# HB-Dis-EP-42BW.net
KiCad netlist of a schematic drawn in EAGLE
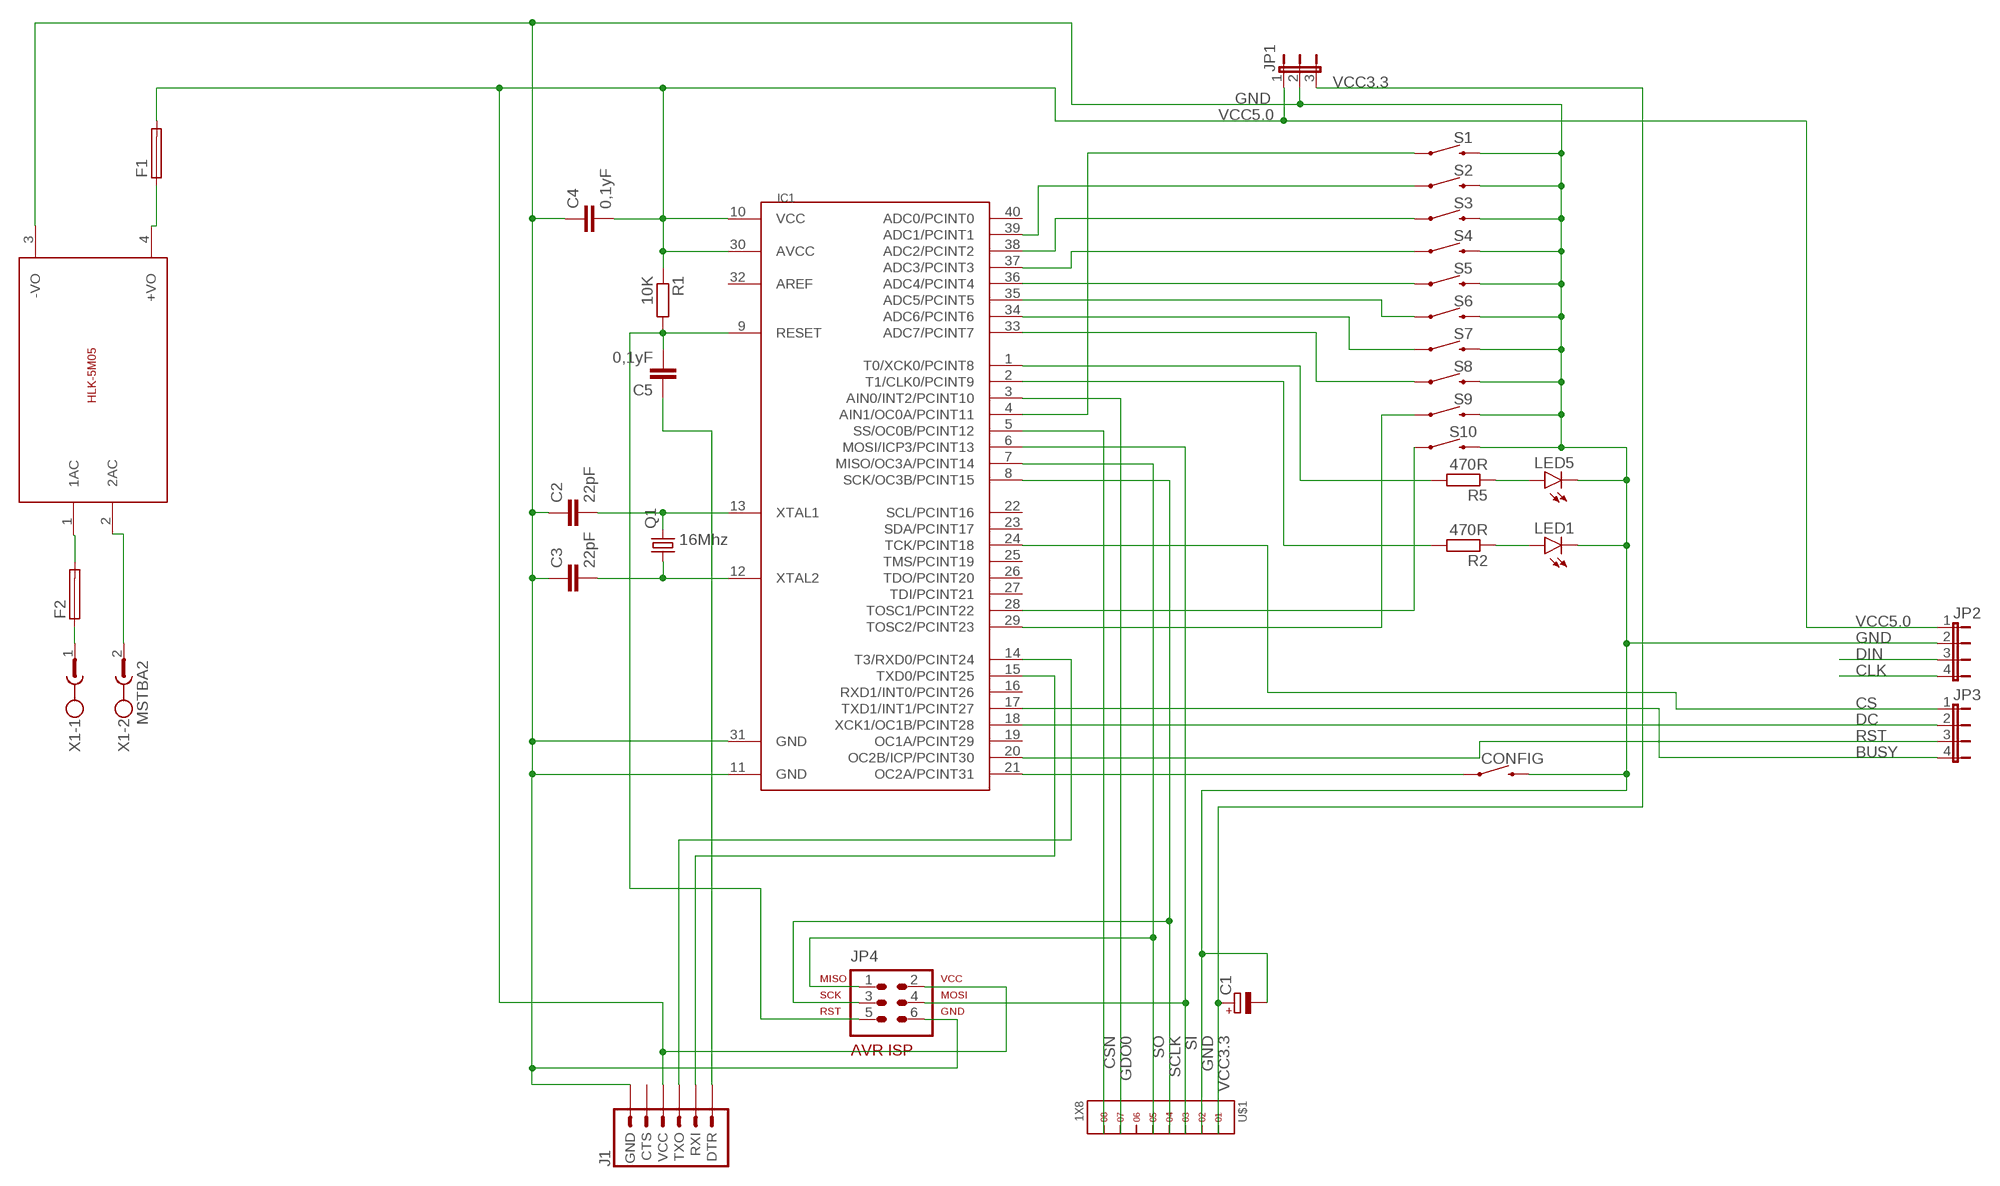
[diagram p0: schematic, sheet 1]

(export (version "E")
  (design (tool "Eeschema 10.0.6"))
  (components
    (comp (ref "C1")
      (value "CPOL-EUE2.5-5")
      (footprint "eagle-import:E2,5-5")
      (libsource (lib "eagle-import") (part "CPOL-EUE2.5-5"))
    )
    (comp (ref "C2")
      (value "22pF")
      (footprint "eagle-import:C025-024X044")
      (libsource (lib "eagle-import") (part "C-EU025-024X044"))
    )
    (comp (ref "C3")
      (value "22pF")
      (footprint "eagle-import:C025-024X044")
      (libsource (lib "eagle-import") (part "C-EU025-024X044"))
    )
    (comp (ref "C4")
      (value "0,1yF")
      (footprint "eagle-import:C025-024X044")
      (libsource (lib "eagle-import") (part "C-EU025-024X044"))
    )
    (comp (ref "C5")
      (value "0,1yF")
      (footprint "eagle-import:C025-024X044")
      (libsource (lib "eagle-import") (part "C-EU025-024X044"))
    )
    (comp (ref "CONFIG")
      (value "MOMENTARY-SWITCH-SPST-PTH-6.0MM-KIT")
      (footprint "eagle-import:TACTILE_SWITCH_PTH_6.0MM_KIT")
      (libsource (lib "eagle-import") (part "MOMENTARY-SWITCH-SPST-PTH-6.0MM-KIT"))
    )
    (comp (ref "F1")
      (value "SH22,5A")
      (footprint "eagle-import:SH22,5A")
      (fields (field (name "MPN") "0031.7701.11"))
      (libsource (lib "eagle-import") (part "SH22,5A"))
    )
    (comp (ref "F2")
      (value "SH22,5A")
      (footprint "eagle-import:SH22,5A")
      (fields (field (name "MPN") "0031.7701.11"))
      (libsource (lib "eagle-import") (part "SH22,5A"))
    )
    (comp (ref "IC1")
      (value "MEGA1284P")
      (footprint "eagle-import:DIL40")
      (libsource (lib "eagle-import") (part "MEGA1284P"))
    )
    (comp (ref "J1")
      (value "6_PIN_SERIAL_TARGETLONGPADS")
      (footprint "eagle-import:1X06_LONGPADS")
      (libsource (lib "eagle-import") (part "6_PIN_SERIAL_TARGETLONGPADS"))
    )
    (comp (ref "JP1")
      (value "JP2E")
      (footprint "eagle-import:JP2")
      (libsource (lib "eagle-import") (part "JP2E"))
    )
    (comp (ref "JP2")
      (value "JP4E")
      (footprint "eagle-import:JP4")
      (libsource (lib "eagle-import") (part "JP4E"))
    )
    (comp (ref "JP3")
      (value "JP4E")
      (footprint "eagle-import:JP4")
      (libsource (lib "eagle-import") (part "JP4E"))
    )
    (comp (ref "JP4")
      (value "AVR-ISP-6VERT")
      (footprint "eagle-import:AVR-ISP-6")
      (libsource (lib "eagle-import") (part "AVR-ISP-6VERT"))
    )
    (comp (ref "LED1")
      (value "LED3MM")
      (footprint "eagle-import:LED3MM")
      (libsource (lib "eagle-import") (part "LED3MM"))
    )
    (comp (ref "LED5")
      (value "LED3MM")
      (footprint "eagle-import:LED3MM")
      (libsource (lib "eagle-import") (part "LED3MM"))
    )
    (comp (ref "Q1")
      (value "16Mhz")
      (footprint "eagle-import:HC49U-V")
      (libsource (lib "eagle-import") (part "CRYSTALHC49U-V"))
    )
    (comp (ref "R1")
      (value "10K")
      (footprint "eagle-import:0309_10")
      (libsource (lib "eagle-import") (part "R-EU_0309/10"))
    )
    (comp (ref "R2")
      (value "470R")
      (footprint "eagle-import:0309_10")
      (libsource (lib "eagle-import") (part "R-EU_0309/10"))
    )
    (comp (ref "R5")
      (value "470R")
      (footprint "eagle-import:0309_10")
      (libsource (lib "eagle-import") (part "R-EU_0309/10"))
    )
    (comp (ref "S1")
      (value "MOMENTARY-SWITCH-SPST-PTH-6.0MM-KIT")
      (footprint "eagle-import:TACTILE_SWITCH_PTH_6.0MM_KIT")
      (libsource (lib "eagle-import") (part "MOMENTARY-SWITCH-SPST-PTH-6.0MM-KIT"))
    )
    (comp (ref "S2")
      (value "MOMENTARY-SWITCH-SPST-PTH-6.0MM-KIT")
      (footprint "eagle-import:TACTILE_SWITCH_PTH_6.0MM_KIT")
      (libsource (lib "eagle-import") (part "MOMENTARY-SWITCH-SPST-PTH-6.0MM-KIT"))
    )
    (comp (ref "S3")
      (value "MOMENTARY-SWITCH-SPST-PTH-6.0MM-KIT")
      (footprint "eagle-import:TACTILE_SWITCH_PTH_6.0MM_KIT")
      (libsource (lib "eagle-import") (part "MOMENTARY-SWITCH-SPST-PTH-6.0MM-KIT"))
    )
    (comp (ref "S4")
      (value "MOMENTARY-SWITCH-SPST-PTH-6.0MM-KIT")
      (footprint "eagle-import:TACTILE_SWITCH_PTH_6.0MM_KIT")
      (libsource (lib "eagle-import") (part "MOMENTARY-SWITCH-SPST-PTH-6.0MM-KIT"))
    )
    (comp (ref "S5")
      (value "MOMENTARY-SWITCH-SPST-PTH-6.0MM-KIT")
      (footprint "eagle-import:TACTILE_SWITCH_PTH_6.0MM_KIT")
      (libsource (lib "eagle-import") (part "MOMENTARY-SWITCH-SPST-PTH-6.0MM-KIT"))
    )
    (comp (ref "S6")
      (value "MOMENTARY-SWITCH-SPST-PTH-6.0MM-KIT")
      (footprint "eagle-import:TACTILE_SWITCH_PTH_6.0MM_KIT")
      (libsource (lib "eagle-import") (part "MOMENTARY-SWITCH-SPST-PTH-6.0MM-KIT"))
    )
    (comp (ref "S7")
      (value "MOMENTARY-SWITCH-SPST-PTH-6.0MM-KIT")
      (footprint "eagle-import:TACTILE_SWITCH_PTH_6.0MM_KIT")
      (libsource (lib "eagle-import") (part "MOMENTARY-SWITCH-SPST-PTH-6.0MM-KIT"))
    )
    (comp (ref "S8")
      (value "MOMENTARY-SWITCH-SPST-PTH-6.0MM-KIT")
      (footprint "eagle-import:TACTILE_SWITCH_PTH_6.0MM_KIT")
      (libsource (lib "eagle-import") (part "MOMENTARY-SWITCH-SPST-PTH-6.0MM-KIT"))
    )
    (comp (ref "S9")
      (value "MOMENTARY-SWITCH-SPST-PTH-6.0MM-KIT")
      (footprint "eagle-import:TACTILE_SWITCH_PTH_6.0MM_KIT")
      (libsource (lib "eagle-import") (part "MOMENTARY-SWITCH-SPST-PTH-6.0MM-KIT"))
    )
    (comp (ref "S10")
      (value "MOMENTARY-SWITCH-SPST-PTH-6.0MM-KIT")
      (footprint "eagle-import:TACTILE_SWITCH_PTH_6.0MM_KIT")
      (libsource (lib "eagle-import") (part "MOMENTARY-SWITCH-SPST-PTH-6.0MM-KIT"))
    )
    (comp (ref "U$1")
      (value "1X8")
      (footprint "eagle-import:1X8")
      (libsource (lib "eagle-import") (part "1X8"))
    )
    (comp (ref "U$3")
      (value "5VDC/5W")
      (footprint "eagle-import:HLK-5M05")
      (libsource (lib "eagle-import") (part "HLK-5M05"))
    )
    (comp (ref "X1")
      (value "MSTBA2")
      (footprint "eagle-import:MSTBA2")
      (fields (field (name "MF") "FARNELL") (field (name "MPN") "1757242"))
      (libsource (lib "eagle-import") (part "MSTBA2"))
    )
  )
  (nets
    (net (code "1") (name "/BUSY") (class "Default")
      (node (ref "IC1") (pin "17") (pinfunction "TXD1/INT1/PCINT27_17") (pintype "bidirectional"))
      (node (ref "JP3") (pin "4") (pinfunction "4_4") (pintype "passive"))
    )
    (net (code "2") (name "/CLK") (class "Default")
      (node (ref "JP2") (pin "4") (pinfunction "4_4") (pintype "passive"))
    )
    (net (code "3") (name "/CS") (class "Default")
      (node (ref "IC1") (pin "24") (pinfunction "TCK/PCINT18_24") (pintype "bidirectional"))
      (node (ref "JP3") (pin "1") (pinfunction "1_1") (pintype "passive"))
    )
    (net (code "4") (name "/CSN") (class "Default")
      (node (ref "IC1") (pin "5") (pinfunction "SS/OC0B/PCINT12_5") (pintype "bidirectional"))
      (node (ref "U$1") (pin "8") (pinfunction "8_8") (pintype "bidirectional"))
    )
    (net (code "5") (name "/DC") (class "Default")
      (node (ref "IC1") (pin "18") (pinfunction "XCK1/OC1B/PCINT28_18") (pintype "bidirectional"))
      (node (ref "JP3") (pin "2") (pinfunction "2_2") (pintype "passive"))
    )
    (net (code "6") (name "/DIN") (class "Default")
      (node (ref "JP2") (pin "3") (pinfunction "3_3") (pintype "passive"))
    )
    (net (code "7") (name "/GDO0") (class "Default")
      (node (ref "IC1") (pin "3") (pinfunction "AIN0/INT2/PCINT10_3") (pintype "bidirectional"))
      (node (ref "U$1") (pin "7") (pinfunction "7_7") (pintype "bidirectional"))
    )
    (net (code "8") (name "/GND") (class "Default")
      (node (ref "C1") (pin "-") (pinfunction "-_-") (pintype "passive"))
      (node (ref "C2") (pin "1") (pinfunction "1_1") (pintype "passive"))
      (node (ref "C3") (pin "1") (pinfunction "1_1") (pintype "passive"))
      (node (ref "C4") (pin "1") (pinfunction "1_1") (pintype "passive"))
      (node (ref "CONFIG") (pin "3") (pinfunction "2_3") (pintype "passive"))
      (node (ref "IC1") (pin "11") (pinfunction "GND_11") (pintype "bidirectional"))
      (node (ref "IC1") (pin "31") (pinfunction "GND_31") (pintype "bidirectional"))
      (node (ref "J1") (pin "6") (pinfunction "GND_6") (pintype "passive"))
      (node (ref "JP1") (pin "2") (pinfunction "2_2") (pintype "passive"))
      (node (ref "JP2") (pin "2") (pinfunction "2_2") (pintype "passive"))
      (node (ref "JP4") (pin "6") (pinfunction "6_6") (pintype "passive"))
      (node (ref "LED1") (pin "K") (pinfunction "C_K") (pintype "passive"))
      (node (ref "LED5") (pin "K") (pinfunction "C_K") (pintype "passive"))
      (node (ref "S1") (pin "3") (pinfunction "2_3") (pintype "passive"))
      (node (ref "S10") (pin "3") (pinfunction "2_3") (pintype "passive"))
      (node (ref "S2") (pin "3") (pinfunction "2_3") (pintype "passive"))
      (node (ref "S3") (pin "3") (pinfunction "2_3") (pintype "passive"))
      (node (ref "S4") (pin "3") (pinfunction "2_3") (pintype "passive"))
      (node (ref "S5") (pin "3") (pinfunction "2_3") (pintype "passive"))
      (node (ref "S6") (pin "3") (pinfunction "2_3") (pintype "passive"))
      (node (ref "S7") (pin "3") (pinfunction "2_3") (pintype "passive"))
      (node (ref "S8") (pin "3") (pinfunction "2_3") (pintype "passive"))
      (node (ref "S9") (pin "3") (pinfunction "2_3") (pintype "passive"))
      (node (ref "U$1") (pin "2") (pinfunction "2_2") (pintype "bidirectional"))
      (node (ref "U$3") (pin "3") (pinfunction "-VO_3") (pintype "bidirectional"))
    )
    (net (code "9") (name "/RST") (class "Default")
      (node (ref "IC1") (pin "20") (pinfunction "OC2B/ICP/PCINT30_20") (pintype "bidirectional"))
      (node (ref "JP3") (pin "3") (pinfunction "3_3") (pintype "passive"))
    )
    (net (code "10") (name "/SCLK") (class "Default")
      (node (ref "IC1") (pin "8") (pinfunction "SCK/OC3B/PCINT15_8") (pintype "bidirectional"))
      (node (ref "JP4") (pin "3") (pinfunction "3_3") (pintype "passive"))
      (node (ref "U$1") (pin "4") (pinfunction "4_4") (pintype "bidirectional"))
    )
    (net (code "11") (name "/SI") (class "Default")
      (node (ref "IC1") (pin "6") (pinfunction "MOSI/ICP3/PCINT13_6") (pintype "bidirectional"))
      (node (ref "JP4") (pin "4") (pinfunction "4_4") (pintype "passive"))
      (node (ref "U$1") (pin "3") (pinfunction "3_3") (pintype "bidirectional"))
    )
    (net (code "12") (name "/SO") (class "Default")
      (node (ref "IC1") (pin "7") (pinfunction "MISO/OC3A/PCINT14_7") (pintype "bidirectional"))
      (node (ref "JP4") (pin "1") (pinfunction "1_1") (pintype "passive"))
      (node (ref "U$1") (pin "5") (pinfunction "5_5") (pintype "bidirectional"))
    )
    (net (code "13") (name "/VCC3.3") (class "Default")
      (node (ref "C1") (pin "+") (pinfunction "+_+") (pintype "passive"))
      (node (ref "JP1") (pin "3") (pinfunction "3_3") (pintype "passive"))
      (node (ref "U$1") (pin "1") (pinfunction "1_1") (pintype "bidirectional"))
    )
    (net (code "14") (name "/VCC5.0") (class "Default")
      (node (ref "C4") (pin "2") (pinfunction "2_2") (pintype "passive"))
      (node (ref "F1") (pin "2") (pinfunction "2_2") (pintype "passive"))
      (node (ref "IC1") (pin "10") (pinfunction "VCC_10") (pintype "bidirectional"))
      (node (ref "IC1") (pin "30") (pinfunction "AVCC_30") (pintype "bidirectional"))
      (node (ref "J1") (pin "4") (pinfunction "VCC_4") (pintype "passive"))
      (node (ref "JP1") (pin "1") (pinfunction "1_1") (pintype "passive"))
      (node (ref "JP2") (pin "1") (pinfunction "1_1") (pintype "passive"))
      (node (ref "JP4") (pin "2") (pinfunction "2_2") (pintype "passive"))
      (node (ref "R1") (pin "1") (pinfunction "1_1") (pintype "passive"))
    )
    (net (code "15") (name "Net-(F2-Pad1)") (class "Default")
      (node (ref "F2") (pin "1") (pinfunction "1_1") (pintype "passive"))
      (node (ref "X1") (pin "1") (pinfunction "1_1") (pintype "passive"))
    )
    (net (code "16") (name "Net-(IC1-ADC1{slash}PCINT1)") (class "Default")
      (node (ref "IC1") (pin "39") (pinfunction "ADC1/PCINT1_39") (pintype "bidirectional"))
      (node (ref "S2") (pin "1") (pinfunction "1_1") (pintype "passive"))
    )
    (net (code "17") (name "Net-(IC1-ADC2{slash}PCINT2)") (class "Default")
      (node (ref "IC1") (pin "38") (pinfunction "ADC2/PCINT2_38") (pintype "bidirectional"))
      (node (ref "S3") (pin "1") (pinfunction "1_1") (pintype "passive"))
    )
    (net (code "18") (name "Net-(IC1-ADC3{slash}PCINT3)") (class "Default")
      (node (ref "IC1") (pin "37") (pinfunction "ADC3/PCINT3_37") (pintype "bidirectional"))
      (node (ref "S4") (pin "1") (pinfunction "1_1") (pintype "passive"))
    )
    (net (code "19") (name "Net-(IC1-ADC4{slash}PCINT4)") (class "Default")
      (node (ref "IC1") (pin "36") (pinfunction "ADC4/PCINT4_36") (pintype "bidirectional"))
      (node (ref "S5") (pin "1") (pinfunction "1_1") (pintype "passive"))
    )
    (net (code "20") (name "Net-(IC1-ADC5{slash}PCINT5)") (class "Default")
      (node (ref "IC1") (pin "35") (pinfunction "ADC5/PCINT5_35") (pintype "bidirectional"))
      (node (ref "S6") (pin "1") (pinfunction "1_1") (pintype "passive"))
    )
    (net (code "21") (name "Net-(IC1-ADC6{slash}PCINT6)") (class "Default")
      (node (ref "IC1") (pin "34") (pinfunction "ADC6/PCINT6_34") (pintype "bidirectional"))
      (node (ref "S7") (pin "1") (pinfunction "1_1") (pintype "passive"))
    )
    (net (code "22") (name "Net-(IC1-ADC7{slash}PCINT7)") (class "Default")
      (node (ref "IC1") (pin "33") (pinfunction "ADC7/PCINT7_33") (pintype "bidirectional"))
      (node (ref "S8") (pin "1") (pinfunction "1_1") (pintype "passive"))
    )
    (net (code "23") (name "Net-(IC1-AIN1{slash}OC0A{slash}PCINT11)") (class "Default")
      (node (ref "IC1") (pin "4") (pinfunction "AIN1/OC0A/PCINT11_4") (pintype "bidirectional"))
      (node (ref "S1") (pin "1") (pinfunction "1_1") (pintype "passive"))
    )
    (net (code "24") (name "Net-(IC1-OC2A{slash}PCINT31)") (class "Default")
      (node (ref "CONFIG") (pin "1") (pinfunction "1_1") (pintype "passive"))
      (node (ref "IC1") (pin "21") (pinfunction "OC2A/PCINT31_21") (pintype "bidirectional"))
    )
    (net (code "25") (name "Net-(IC1-RESET)") (class "Default")
      (node (ref "C5") (pin "2") (pinfunction "2_2") (pintype "passive"))
      (node (ref "IC1") (pin "9") (pinfunction "RESET_9") (pintype "bidirectional"))
      (node (ref "JP4") (pin "5") (pinfunction "5_5") (pintype "passive"))
      (node (ref "R1") (pin "2") (pinfunction "2_2") (pintype "passive"))
    )
    (net (code "26") (name "Net-(IC1-T0{slash}XCK0{slash}PCINT8)") (class "Default")
      (node (ref "IC1") (pin "1") (pinfunction "T0/XCK0/PCINT8_1") (pintype "bidirectional"))
      (node (ref "R5") (pin "2") (pinfunction "2_2") (pintype "passive"))
    )
    (net (code "27") (name "Net-(IC1-T1{slash}CLK0{slash}PCINT9)") (class "Default")
      (node (ref "IC1") (pin "2") (pinfunction "T1/CLK0/PCINT9_2") (pintype "bidirectional"))
      (node (ref "R2") (pin "2") (pinfunction "2_2") (pintype "passive"))
    )
    (net (code "28") (name "Net-(IC1-T3{slash}RXD0{slash}PCINT24)") (class "Default")
      (node (ref "IC1") (pin "14") (pinfunction "T3/RXD0/PCINT24_14") (pintype "bidirectional"))
      (node (ref "J1") (pin "3") (pinfunction "TXO_3") (pintype "passive"))
    )
    (net (code "29") (name "Net-(IC1-TOSC1{slash}PCINT22)") (class "Default")
      (node (ref "IC1") (pin "28") (pinfunction "TOSC1/PCINT22_28") (pintype "bidirectional"))
      (node (ref "S10") (pin "1") (pinfunction "1_1") (pintype "passive"))
    )
    (net (code "30") (name "Net-(IC1-TOSC2{slash}PCINT23)") (class "Default")
      (node (ref "IC1") (pin "29") (pinfunction "TOSC2/PCINT23_29") (pintype "bidirectional"))
      (node (ref "S9") (pin "1") (pinfunction "1_1") (pintype "passive"))
    )
    (net (code "31") (name "Net-(IC1-TXD0{slash}PCINT25)") (class "Default")
      (node (ref "IC1") (pin "15") (pinfunction "TXD0/PCINT25_15") (pintype "bidirectional"))
      (node (ref "J1") (pin "2") (pinfunction "RXI_2") (pintype "passive"))
    )
    (net (code "32") (name "Net-(IC1-XTAL1)") (class "Default")
      (node (ref "C2") (pin "2") (pinfunction "2_2") (pintype "passive"))
      (node (ref "IC1") (pin "13") (pinfunction "XTAL1_13") (pintype "bidirectional"))
      (node (ref "Q1") (pin "2") (pinfunction "2_2") (pintype "passive"))
    )
    (net (code "33") (name "Net-(IC1-XTAL2)") (class "Default")
      (node (ref "C3") (pin "2") (pinfunction "2_2") (pintype "passive"))
      (node (ref "IC1") (pin "12") (pinfunction "XTAL2_12") (pintype "bidirectional"))
      (node (ref "Q1") (pin "1") (pinfunction "1_1") (pintype "passive"))
    )
    (net (code "34") (name "Net-(J1-DTR)") (class "Default")
      (node (ref "C5") (pin "1") (pinfunction "1_1") (pintype "passive"))
      (node (ref "J1") (pin "1") (pinfunction "DTR_1") (pintype "passive"))
    )
    (net (code "35") (name "Net-(LED1-PadA)") (class "Default")
      (node (ref "LED1") (pin "A") (pinfunction "A_A") (pintype "passive"))
      (node (ref "R2") (pin "1") (pinfunction "1_1") (pintype "passive"))
    )
    (net (code "36") (name "Net-(LED5-PadA)") (class "Default")
      (node (ref "LED5") (pin "A") (pinfunction "A_A") (pintype "passive"))
      (node (ref "R5") (pin "1") (pinfunction "1_1") (pintype "passive"))
    )
    (net (code "37") (name "Net-(U$3-+VO)") (class "Default")
      (node (ref "F1") (pin "1") (pinfunction "1_1") (pintype "passive"))
      (node (ref "U$3") (pin "4") (pinfunction "+VO_4") (pintype "bidirectional"))
    )
    (net (code "38") (name "Net-(U$3-1AC)") (class "Default")
      (node (ref "F2") (pin "2") (pinfunction "2_2") (pintype "passive"))
      (node (ref "U$3") (pin "1") (pinfunction "1AC_1") (pintype "bidirectional"))
    )
    (net (code "39") (name "Net-(U$3-2AC)") (class "Default")
      (node (ref "U$3") (pin "2") (pinfunction "2AC_2") (pintype "bidirectional"))
      (node (ref "X1") (pin "2") (pinfunction "1_2") (pintype "passive"))
    )
    (net (code "40") (name "unconnected-(IC1-ADC0{slash}PCINT0-Pad40)") (class "Default")
      (node (ref "IC1") (pin "40") (pinfunction "ADC0/PCINT0_40") (pintype "bidirectional"))
    )
    (net (code "41") (name "unconnected-(IC1-AREF-Pad32)") (class "Default")
      (node (ref "IC1") (pin "32") (pinfunction "AREF_32") (pintype "bidirectional"))
    )
    (net (code "42") (name "unconnected-(IC1-OC1A{slash}PCINT29-Pad19)") (class "Default")
      (node (ref "IC1") (pin "19") (pinfunction "OC1A/PCINT29_19") (pintype "bidirectional"))
    )
    (net (code "43") (name "unconnected-(IC1-RXD1{slash}INT0{slash}PCINT26-Pad16)") (class "Default")
      (node (ref "IC1") (pin "16") (pinfunction "RXD1/INT0/PCINT26_16") (pintype "bidirectional"))
    )
    (net (code "44") (name "unconnected-(IC1-SCL{slash}PCINT16-Pad22)") (class "Default")
      (node (ref "IC1") (pin "22") (pinfunction "SCL/PCINT16_22") (pintype "bidirectional"))
    )
    (net (code "45") (name "unconnected-(IC1-SDA{slash}PCINT17-Pad23)") (class "Default")
      (node (ref "IC1") (pin "23") (pinfunction "SDA/PCINT17_23") (pintype "bidirectional"))
    )
    (net (code "46") (name "unconnected-(IC1-TDI{slash}PCINT21-Pad27)") (class "Default")
      (node (ref "IC1") (pin "27") (pinfunction "TDI/PCINT21_27") (pintype "bidirectional"))
    )
    (net (code "47") (name "unconnected-(IC1-TDO{slash}PCINT20-Pad26)") (class "Default")
      (node (ref "IC1") (pin "26") (pinfunction "TDO/PCINT20_26") (pintype "bidirectional"))
    )
    (net (code "48") (name "unconnected-(IC1-TMS{slash}PCINT19-Pad25)") (class "Default")
      (node (ref "IC1") (pin "25") (pinfunction "TMS/PCINT19_25") (pintype "bidirectional"))
    )
    (net (code "49") (name "unconnected-(J1-CTS-Pad5)") (class "Default")
      (node (ref "J1") (pin "5") (pinfunction "CTS_5") (pintype "passive"))
    )
    (net (code "50") (name "unconnected-(U$1-Pad6)") (class "Default")
      (node (ref "U$1") (pin "6") (pinfunction "6_6") (pintype "bidirectional"))
    )
  )
)
